# v001.net
KiCad netlist of a schematic drawn in EAGLE
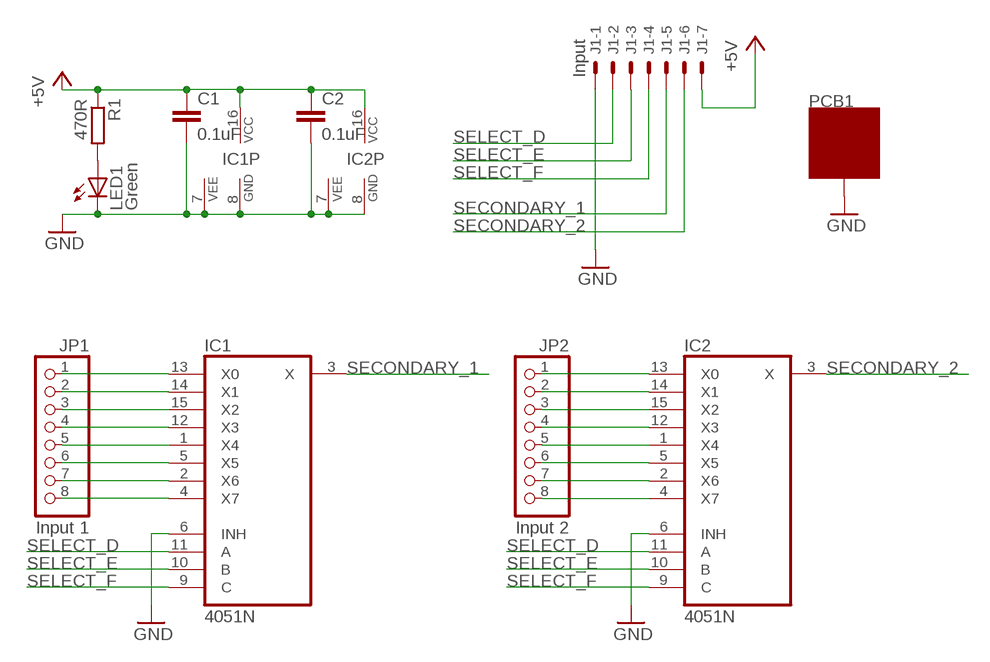
[diagram p0: schematic, sheet 1]

(export (version "E")
  (design (tool "Eeschema 10.0.6"))
  (components
    (comp (ref "C1")
      (value "0.1uF")
      (footprint "eagle-import:C050-024X044")
      (libsource (lib "eagle-import") (part "C-EU050-024X044"))
    )
    (comp (ref "C2")
      (value "0.1uF")
      (footprint "eagle-import:C050-024X044")
      (libsource (lib "eagle-import") (part "C-EU050-024X044"))
    )
    (comp (ref "IC1")
      (value "4051N")
      (footprint "eagle-import:DIL16")
      (libsource (lib "eagle-import") (part "4051N"))
    )
    (comp (ref "IC2")
      (value "4051N")
      (footprint "eagle-import:DIL16")
      (libsource (lib "eagle-import") (part "4051N"))
    )
    (comp (ref "J1")
      (value "Input")
      (footprint "eagle-import:6410-07")
      (libsource (lib "eagle-import") (part "22-?-0727-2071"))
    )
    (comp (ref "JP1")
      (value "Input 1")
      (footprint "eagle-import:1X08")
      (libsource (lib "eagle-import") (part "PINHD-1X8"))
    )
    (comp (ref "JP2")
      (value "Input 2")
      (footprint "eagle-import:1X08")
      (libsource (lib "eagle-import") (part "PINHD-1X8"))
    )
    (comp (ref "LED1")
      (value "Green")
      (footprint "eagle-import:LED3MM")
      (libsource (lib "eagle-import") (part "LED3MM"))
    )
    (comp (ref "PCB1")
      (value "ZZZ_MODULE05X05")
      (footprint "eagle-import:ZZZ_MODULE_05X05")
      (libsource (lib "eagle-import") (part "ZZZ_MODULE05X05"))
    )
    (comp (ref "R1")
      (value "470R")
      (footprint "eagle-import:0207_2V")
      (libsource (lib "eagle-import") (part "R-EU_0207/2V"))
    )
  )
  (nets
    (net (code "1") (name "+5V") (class "Default")
      (node (ref "C1") (pin "1") (pinfunction "1_1") (pintype "passive"))
      (node (ref "C2") (pin "1") (pinfunction "1_1") (pintype "passive"))
      (node (ref "IC1") (pin "16") (pinfunction "VCC_16") (pintype "power_in"))
      (node (ref "IC2") (pin "16") (pinfunction "VCC_16") (pintype "power_in"))
      (node (ref "J1") (pin "7") (pinfunction "S_7") (pintype "passive"))
      (node (ref "R1") (pin "1") (pinfunction "1_1") (pintype "passive"))
    )
    (net (code "2") (name "/SECONDARY_1") (class "Default")
      (node (ref "IC1") (pin "3") (pinfunction "X_3") (pintype "bidirectional"))
      (node (ref "J1") (pin "5") (pinfunction "S_5") (pintype "passive"))
    )
    (net (code "3") (name "/SECONDARY_2") (class "Default")
      (node (ref "IC2") (pin "3") (pinfunction "X_3") (pintype "bidirectional"))
      (node (ref "J1") (pin "6") (pinfunction "S_6") (pintype "passive"))
    )
    (net (code "4") (name "/SELECT_D") (class "Default")
      (node (ref "IC1") (pin "11") (pinfunction "A_11") (pintype "input"))
      (node (ref "IC2") (pin "11") (pinfunction "A_11") (pintype "input"))
      (node (ref "J1") (pin "2") (pinfunction "S_2") (pintype "passive"))
    )
    (net (code "5") (name "/SELECT_E") (class "Default")
      (node (ref "IC1") (pin "10") (pinfunction "B_10") (pintype "input"))
      (node (ref "IC2") (pin "10") (pinfunction "B_10") (pintype "input"))
      (node (ref "J1") (pin "3") (pinfunction "S_3") (pintype "passive"))
    )
    (net (code "6") (name "/SELECT_F") (class "Default")
      (node (ref "IC1") (pin "9") (pinfunction "C_9") (pintype "input"))
      (node (ref "IC2") (pin "9") (pinfunction "C_9") (pintype "input"))
      (node (ref "J1") (pin "4") (pinfunction "S_4") (pintype "passive"))
    )
    (net (code "7") (name "GND") (class "Default")
      (node (ref "C1") (pin "2") (pinfunction "2_2") (pintype "passive"))
      (node (ref "C2") (pin "2") (pinfunction "2_2") (pintype "passive"))
      (node (ref "IC1") (pin "6") (pinfunction "INH_6") (pintype "input"))
      (node (ref "IC1") (pin "7") (pinfunction "VEE_7") (pintype "power_in"))
      (node (ref "IC1") (pin "8") (pinfunction "GND_8") (pintype "power_in"))
      (node (ref "IC2") (pin "6") (pinfunction "INH_6") (pintype "input"))
      (node (ref "IC2") (pin "7") (pinfunction "VEE_7") (pintype "power_in"))
      (node (ref "IC2") (pin "8") (pinfunction "GND_8") (pintype "power_in"))
      (node (ref "J1") (pin "1") (pinfunction "S_1") (pintype "passive"))
      (node (ref "LED1") (pin "K") (pinfunction "C_K") (pintype "passive"))
      (node (ref "PCB1") (pin "GND@1") (pinfunction "GND_GND@1") (pintype "power_in"))
      (node (ref "PCB1") (pin "GND@2") (pinfunction "GND_GND@2") (pintype "power_in"))
      (node (ref "PCB1") (pin "GND@3") (pinfunction "GND_GND@3") (pintype "power_in"))
      (node (ref "PCB1") (pin "GND@4") (pinfunction "GND_GND@4") (pintype "power_in"))
      (node (ref "PCB1") (pin "GND@5") (pinfunction "GND_GND@5") (pintype "power_in"))
      (node (ref "PCB1") (pin "GND@6") (pinfunction "GND_GND@6") (pintype "power_in"))
      (node (ref "PCB1") (pin "GND@7") (pinfunction "GND_GND@7") (pintype "power_in"))
      (node (ref "PCB1") (pin "GND@8") (pinfunction "GND_GND@8") (pintype "power_in"))
    )
    (net (code "8") (name "Net-(IC1A-X0)") (class "Default")
      (node (ref "IC1") (pin "13") (pinfunction "X0_13") (pintype "bidirectional"))
      (node (ref "JP1") (pin "1") (pinfunction "1_1") (pintype "passive"))
    )
    (net (code "9") (name "Net-(IC1A-X1)") (class "Default")
      (node (ref "IC1") (pin "14") (pinfunction "X1_14") (pintype "bidirectional"))
      (node (ref "JP1") (pin "2") (pinfunction "2_2") (pintype "passive"))
    )
    (net (code "10") (name "Net-(IC1A-X2)") (class "Default")
      (node (ref "IC1") (pin "15") (pinfunction "X2_15") (pintype "bidirectional"))
      (node (ref "JP1") (pin "3") (pinfunction "3_3") (pintype "passive"))
    )
    (net (code "11") (name "Net-(IC1A-X3)") (class "Default")
      (node (ref "IC1") (pin "12") (pinfunction "X3_12") (pintype "bidirectional"))
      (node (ref "JP1") (pin "4") (pinfunction "4_4") (pintype "passive"))
    )
    (net (code "12") (name "Net-(IC1A-X4)") (class "Default")
      (node (ref "IC1") (pin "1") (pinfunction "X4_1") (pintype "bidirectional"))
      (node (ref "JP1") (pin "5") (pinfunction "5_5") (pintype "passive"))
    )
    (net (code "13") (name "Net-(IC1A-X5)") (class "Default")
      (node (ref "IC1") (pin "5") (pinfunction "X5_5") (pintype "bidirectional"))
      (node (ref "JP1") (pin "6") (pinfunction "6_6") (pintype "passive"))
    )
    (net (code "14") (name "Net-(IC1A-X6)") (class "Default")
      (node (ref "IC1") (pin "2") (pinfunction "X6_2") (pintype "bidirectional"))
      (node (ref "JP1") (pin "7") (pinfunction "7_7") (pintype "passive"))
    )
    (net (code "15") (name "Net-(IC1A-X7)") (class "Default")
      (node (ref "IC1") (pin "4") (pinfunction "X7_4") (pintype "bidirectional"))
      (node (ref "JP1") (pin "8") (pinfunction "8_8") (pintype "passive"))
    )
    (net (code "16") (name "Net-(IC2A-X0)") (class "Default")
      (node (ref "IC2") (pin "13") (pinfunction "X0_13") (pintype "bidirectional"))
      (node (ref "JP2") (pin "1") (pinfunction "1_1") (pintype "passive"))
    )
    (net (code "17") (name "Net-(IC2A-X1)") (class "Default")
      (node (ref "IC2") (pin "14") (pinfunction "X1_14") (pintype "bidirectional"))
      (node (ref "JP2") (pin "2") (pinfunction "2_2") (pintype "passive"))
    )
    (net (code "18") (name "Net-(IC2A-X2)") (class "Default")
      (node (ref "IC2") (pin "15") (pinfunction "X2_15") (pintype "bidirectional"))
      (node (ref "JP2") (pin "3") (pinfunction "3_3") (pintype "passive"))
    )
    (net (code "19") (name "Net-(IC2A-X3)") (class "Default")
      (node (ref "IC2") (pin "12") (pinfunction "X3_12") (pintype "bidirectional"))
      (node (ref "JP2") (pin "4") (pinfunction "4_4") (pintype "passive"))
    )
    (net (code "20") (name "Net-(IC2A-X4)") (class "Default")
      (node (ref "IC2") (pin "1") (pinfunction "X4_1") (pintype "bidirectional"))
      (node (ref "JP2") (pin "5") (pinfunction "5_5") (pintype "passive"))
    )
    (net (code "21") (name "Net-(IC2A-X5)") (class "Default")
      (node (ref "IC2") (pin "5") (pinfunction "X5_5") (pintype "bidirectional"))
      (node (ref "JP2") (pin "6") (pinfunction "6_6") (pintype "passive"))
    )
    (net (code "22") (name "Net-(IC2A-X6)") (class "Default")
      (node (ref "IC2") (pin "2") (pinfunction "X6_2") (pintype "bidirectional"))
      (node (ref "JP2") (pin "7") (pinfunction "7_7") (pintype "passive"))
    )
    (net (code "23") (name "Net-(IC2A-X7)") (class "Default")
      (node (ref "IC2") (pin "4") (pinfunction "X7_4") (pintype "bidirectional"))
      (node (ref "JP2") (pin "8") (pinfunction "8_8") (pintype "passive"))
    )
    (net (code "24") (name "Net-(LED1-PadA)") (class "Default")
      (node (ref "LED1") (pin "A") (pinfunction "A_A") (pintype "passive"))
      (node (ref "R1") (pin "2") (pinfunction "2_2") (pintype "passive"))
    )
  )
)
